# tx.net
KiCad netlist of a schematic drawn in EAGLE
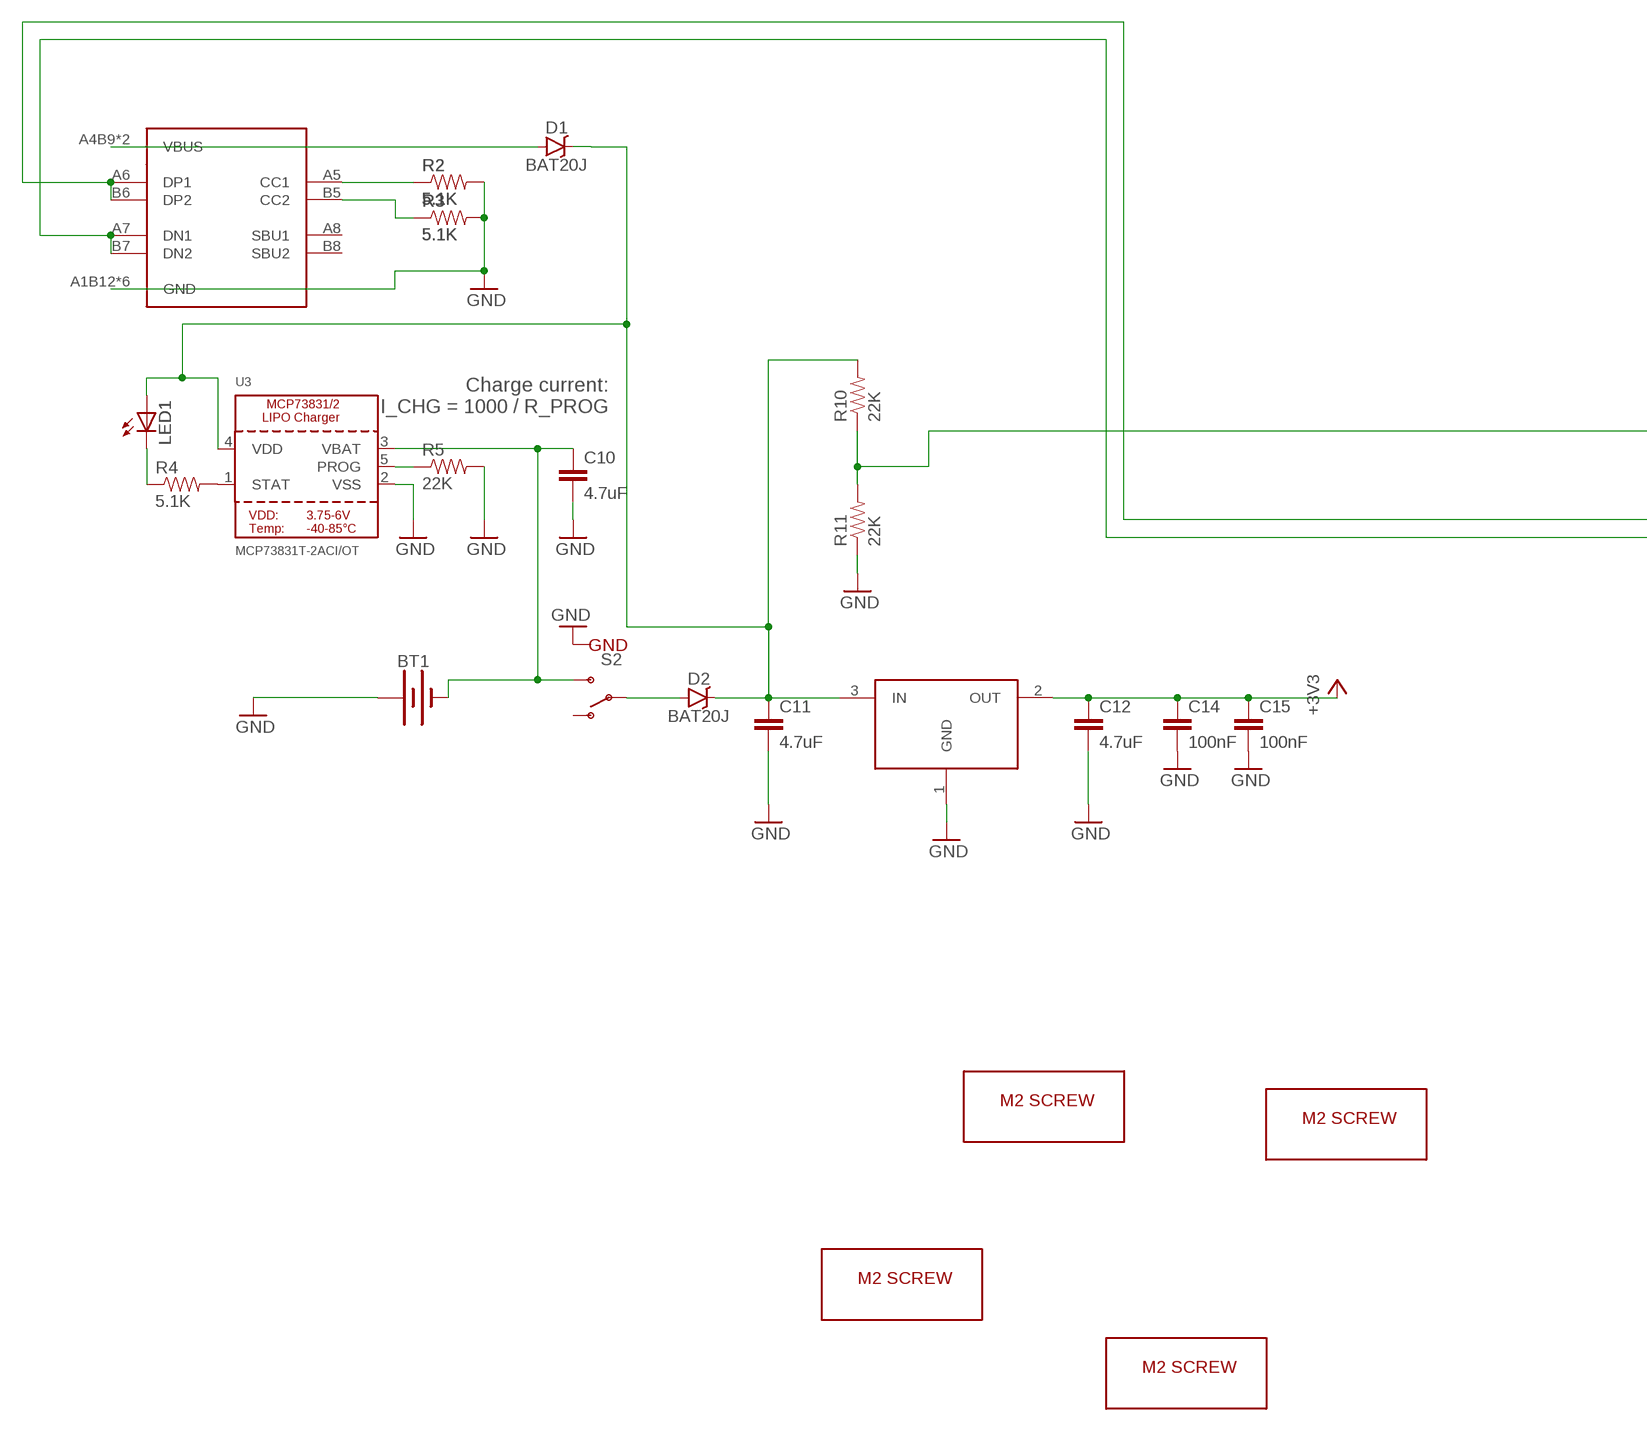
[diagram p0: schematic, sheet 1, part 1 of 2]
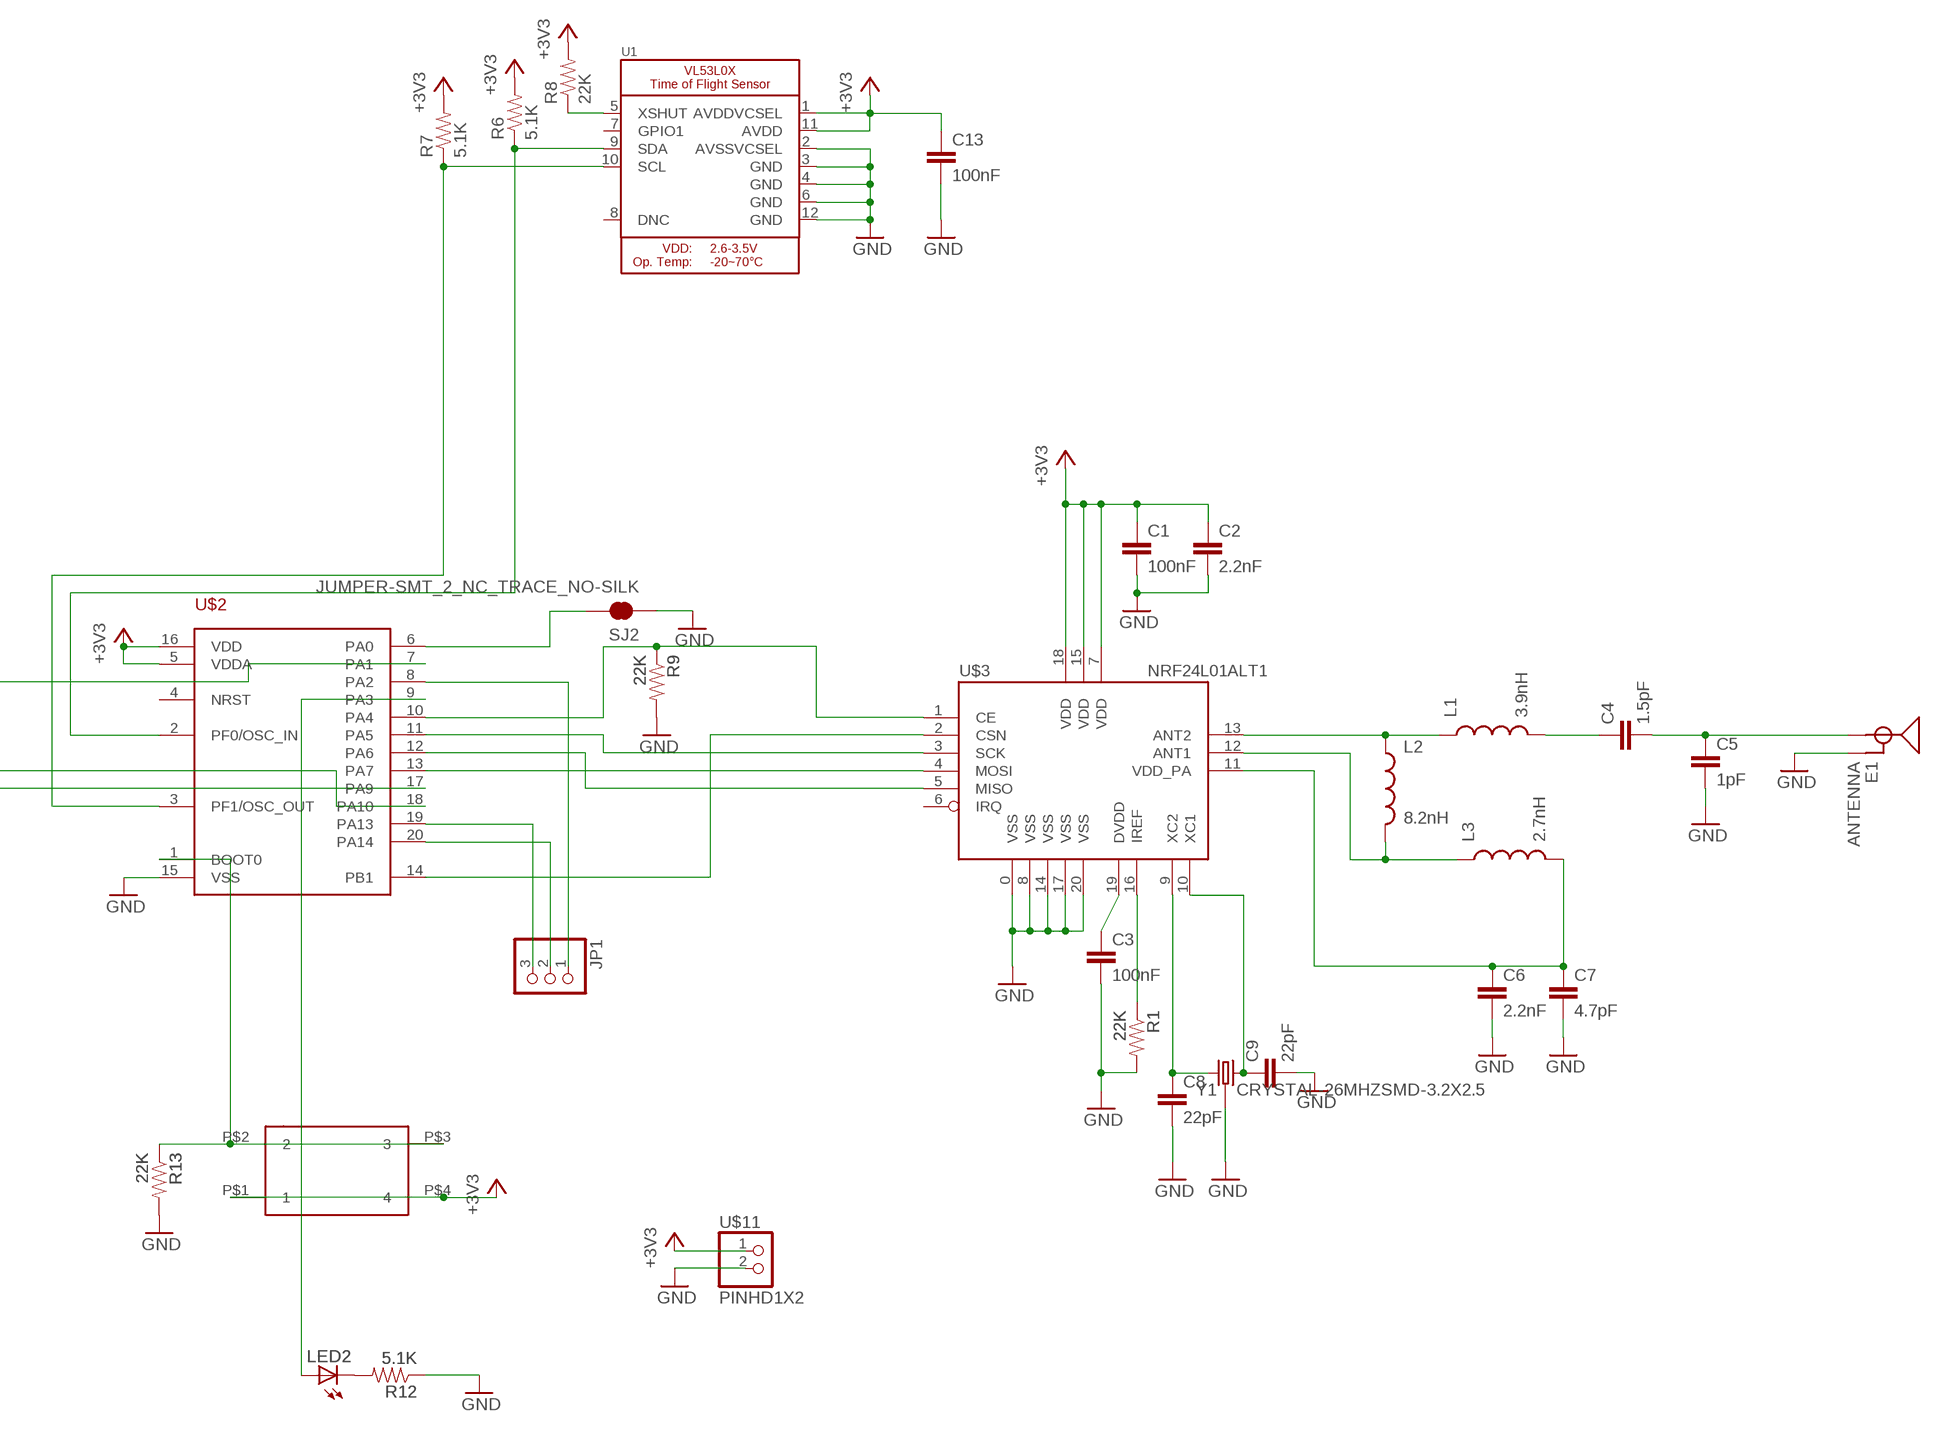
[diagram p1: schematic, sheet 1, part 2 of 2]

(export (version "E")
  (design (tool "Eeschema 10.0.6"))
  (components
    (comp (ref "BT1")
      (value "TX_SPARKFUN-BATTERIES_BATTERY-24.5MM_PTH")
      (footprint "eagle-import:TX_SPARKFUN-BATTERIES_BATTCON_24.5MM_PTH")
      (libsource (lib "eagle-import") (part "TX_SPARKFUN-BATTERIES_BATTERY-24.5MM_PTH"))
    )
    (comp (ref "C1")
      (value "100nF")
      (footprint "eagle-import:0805")
      (libsource (lib "eagle-import") (part "clock_CAP0805"))
    )
    (comp (ref "C2")
      (value "2.2nF")
      (footprint "eagle-import:0805")
      (libsource (lib "eagle-import") (part "clock_CAP0805"))
    )
    (comp (ref "C3")
      (value "100nF")
      (footprint "eagle-import:0805")
      (libsource (lib "eagle-import") (part "clock_CAP0805"))
    )
    (comp (ref "C4")
      (value "1.5pF")
      (footprint "eagle-import:0805")
      (libsource (lib "eagle-import") (part "clock_CAP0805"))
    )
    (comp (ref "C5")
      (value "1pF")
      (footprint "eagle-import:0805")
      (libsource (lib "eagle-import") (part "clock_CAP0805"))
    )
    (comp (ref "C6")
      (value "2.2nF")
      (footprint "eagle-import:0805")
      (libsource (lib "eagle-import") (part "clock_CAP0805"))
    )
    (comp (ref "C7")
      (value "4.7pF")
      (footprint "eagle-import:0805")
      (libsource (lib "eagle-import") (part "clock_CAP0805"))
    )
    (comp (ref "C8")
      (value "22pF")
      (footprint "eagle-import:0805")
      (libsource (lib "eagle-import") (part "clock_CAP0805"))
    )
    (comp (ref "C9")
      (value "22pF")
      (footprint "eagle-import:0805")
      (libsource (lib "eagle-import") (part "clock_CAP0805"))
    )
    (comp (ref "C10")
      (value "4.7uF")
      (footprint "eagle-import:0805")
      (libsource (lib "eagle-import") (part "CAP0805"))
    )
    (comp (ref "C11")
      (value "4.7uF")
      (footprint "eagle-import:0805")
      (libsource (lib "eagle-import") (part "clock_CAP0805"))
    )
    (comp (ref "C12")
      (value "4.7uF")
      (footprint "eagle-import:0805")
      (libsource (lib "eagle-import") (part "clock_CAP0805"))
    )
    (comp (ref "C13")
      (value "100nF")
      (footprint "eagle-import:0805")
      (libsource (lib "eagle-import") (part "clock_CAP0805"))
    )
    (comp (ref "C14")
      (value "100nF")
      (footprint "eagle-import:0805")
      (libsource (lib "eagle-import") (part "clock_CAP0805"))
    )
    (comp (ref "C15")
      (value "100nF")
      (footprint "eagle-import:0805")
      (libsource (lib "eagle-import") (part "clock_CAP0805"))
    )
    (comp (ref "D1")
      (value "BAT20J")
      (footprint "eagle-import:SOD-323")
      (libsource (lib "eagle-import") (part "DIODE-SCHOTTKY-BAT20J"))
    )
    (comp (ref "D2")
      (value "BAT20J")
      (footprint "eagle-import:SOD-323")
      (libsource (lib "eagle-import") (part "DIODE-SCHOTTKY-BAT20J"))
    )
    (comp (ref "E1")
      (value "ANTENNA")
      (footprint "eagle-import:TRACE_ANTENNA_2.4GHZ_25.7MM_TUNED")
      (libsource (lib "eagle-import") (part "ANTENNATRACE-TUNED"))
    )
    (comp (ref "JP1")
      (value "PINHD-1X3CB")
      (footprint "eagle-import:1X03-CLEANBIG")
      (libsource (lib "eagle-import") (part "PINHD-1X3CB"))
    )
    (comp (ref "L1")
      (value "3.9nH")
      (footprint "eagle-import:0805")
      (libsource (lib "eagle-import") (part "INDUCTOR0805"))
    )
    (comp (ref "L2")
      (value "8.2nH")
      (footprint "eagle-import:0805")
      (libsource (lib "eagle-import") (part "INDUCTOR0805"))
    )
    (comp (ref "L3")
      (value "2.7nH")
      (footprint "eagle-import:0805")
      (libsource (lib "eagle-import") (part "INDUCTOR0805"))
    )
    (comp (ref "LED1")
      (value "LEDCHIP-LED0805")
      (footprint "eagle-import:CHIP-LED0805")
      (libsource (lib "eagle-import") (part "LEDCHIP-LED0805"))
    )
    (comp (ref "LED2")
      (value "LEDCHIP-LED0805")
      (footprint "eagle-import:CHIP-LED0805")
      (libsource (lib "eagle-import") (part "LEDCHIP-LED0805"))
    )
    (comp (ref "R1")
      (value "22K")
      (footprint "eagle-import:0805")
      (libsource (lib "eagle-import") (part "joyAnalog_RESISTOR0805-RES"))
    )
    (comp (ref "R2")
      (value "5.1K")
      (footprint "eagle-import:0805")
      (libsource (lib "eagle-import") (part "joyAnalog_RESISTOR0805-RES"))
    )
    (comp (ref "R3")
      (value "5.1K")
      (footprint "eagle-import:0805")
      (libsource (lib "eagle-import") (part "joyAnalog_RESISTOR0805-RES"))
    )
    (comp (ref "R4")
      (value "5.1K")
      (footprint "eagle-import:0805")
      (libsource (lib "eagle-import") (part "RESISTOR0805-RES"))
    )
    (comp (ref "R5")
      (value "22K")
      (footprint "eagle-import:0805")
      (libsource (lib "eagle-import") (part "RESISTOR0805-RES"))
    )
    (comp (ref "R6")
      (value "5.1K")
      (footprint "eagle-import:0805")
      (libsource (lib "eagle-import") (part "RESISTOR0805-RES"))
    )
    (comp (ref "R7")
      (value "5.1K")
      (footprint "eagle-import:0805")
      (libsource (lib "eagle-import") (part "RESISTOR0805-RES"))
    )
    (comp (ref "R8")
      (value "22K")
      (footprint "eagle-import:0805")
      (libsource (lib "eagle-import") (part "RESISTOR0805-RES"))
    )
    (comp (ref "R9")
      (value "22K")
      (footprint "eagle-import:0805")
      (libsource (lib "eagle-import") (part "joyAnalog_RESISTOR0805-RES"))
    )
    (comp (ref "R10")
      (value "22K")
      (footprint "eagle-import:0805")
      (libsource (lib "eagle-import") (part "RESISTOR0805-RES"))
    )
    (comp (ref "R11")
      (value "22K")
      (footprint "eagle-import:0805")
      (libsource (lib "eagle-import") (part "RESISTOR0805-RES"))
    )
    (comp (ref "R12")
      (value "5.1K")
      (footprint "eagle-import:0805")
      (libsource (lib "eagle-import") (part "joyAnalog_RESISTOR0805-RES"))
    )
    (comp (ref "R13")
      (value "22K")
      (footprint "eagle-import:0805")
      (libsource (lib "eagle-import") (part "joyAnalog_RESISTOR0805-RES"))
    )
    (comp (ref "S2")
      (value "SWITCH-SPDTTDFGDFG")
      (footprint "eagle-import:SWITCH-SPST-SMD-A")
      (libsource (lib "eagle-import") (part "SWITCH-SPDTTDFGDFG"))
    )
    (comp (ref "SJ2")
      (value "JUMPER-SMT_2_NC_TRACE_NO-SILK")
      (footprint "eagle-import:SMT-JUMPER_2_NC_TRACE_NO-SILK")
      (libsource (lib "eagle-import") (part "JUMPER-SMT_2_NC_TRACE_NO-SILK"))
    )
    (comp (ref "U$1")
      (value "M2_SCREW_DEV")
      (footprint "eagle-import:M2_SCREW_FOOT")
      (libsource (lib "eagle-import") (part "M2_SCREW_DEV"))
    )
    (comp (ref "U$2")
      (value "STM32F030F4")
      (footprint "eagle-import:TSSOP20")
      (libsource (lib "eagle-import") (part "STM32F030F4"))
    )
    (comp (ref "U$3")
      (value "NRF24L01ALT1")
      (footprint "eagle-import:QFN20_ALT1")
      (libsource (lib "eagle-import") (part "NRF24L01ALT1"))
    )
    (comp (ref "U$4")
      (value "USBC_16P")
      (footprint "eagle-import:USBC_16P_FOOT")
      (libsource (lib "eagle-import") (part "USBC_16P"))
    )
    (comp (ref "U$9")
      (value "XC6206_DEV")
      (footprint "eagle-import:SOT23R_INFINEON")
      (libsource (lib "eagle-import") (part "XC6206_DEV"))
    )
    (comp (ref "U$10")
      (value "324_SW324_SWITCH_FOOT_HOLE")
      (footprint "eagle-import:342_SWICH_FOOT_HOLE")
      (libsource (lib "eagle-import") (part "324_SW324_SWITCH_FOOT_HOLE"))
    )
    (comp (ref "U$11")
      (value "PINHD1X2")
      (footprint "eagle-import:1X02")
      (libsource (lib "eagle-import") (part "PINHD1X2"))
    )
    (comp (ref "U$12")
      (value "M2_SCREW_DEV")
      (footprint "eagle-import:M2_SCREW_FOOT")
      (libsource (lib "eagle-import") (part "M2_SCREW_DEV"))
    )
    (comp (ref "U$13")
      (value "M2_SCREW_DEV")
      (footprint "eagle-import:M2_SCREW_FOOT")
      (libsource (lib "eagle-import") (part "M2_SCREW_DEV"))
    )
    (comp (ref "U$14")
      (value "M2_SCREW_DEV")
      (footprint "eagle-import:M2_SCREW_FOOT")
      (libsource (lib "eagle-import") (part "M2_SCREW_DEV"))
    )
    (comp (ref "U1")
      (value "VL53L0X")
      (footprint "eagle-import:LGA12_ST")
      (libsource (lib "eagle-import") (part "VL53L0X"))
    )
    (comp (ref "U3")
      (value "MCP73831T-2ACI/OT")
      (footprint "eagle-import:SOT23-5")
      (libsource (lib "eagle-import") (part "MCP73831/2"))
    )
    (comp (ref "Y1")
      (value "CRYSTAL-26MHZSMD-3.2X2.5")
      (footprint "eagle-import:CRYSTAL-SMD-3.2X2.5MM")
      (libsource (lib "eagle-import") (part "CRYSTAL-26MHZSMD-3.2X2.5"))
    )
  )
  (nets
    (net (code "1") (name "+3V3") (class "Default")
      (node (ref "C1") (pin "1") (pinfunction "1_1") (pintype "passive"))
      (node (ref "C12") (pin "1") (pinfunction "1_1") (pintype "passive"))
      (node (ref "C13") (pin "1") (pinfunction "1_1") (pintype "passive"))
      (node (ref "C14") (pin "1") (pinfunction "1_1") (pintype "passive"))
      (node (ref "C15") (pin "1") (pinfunction "1_1") (pintype "passive"))
      (node (ref "C2") (pin "1") (pinfunction "1_1") (pintype "passive"))
      (node (ref "R6") (pin "2") (pinfunction "2_2") (pintype "passive"))
      (node (ref "R7") (pin "2") (pinfunction "2_2") (pintype "passive"))
      (node (ref "R8") (pin "2") (pinfunction "2_2") (pintype "passive"))
      (node (ref "U$10") (pin "P$1") (pinfunction "1_P$1") (pintype "bidirectional"))
      (node (ref "U$10") (pin "P$4") (pinfunction "4_P$4") (pintype "bidirectional"))
      (node (ref "U$11") (pin "1") (pinfunction "1_1") (pintype "passive"))
      (node (ref "U$2") (pin "16") (pinfunction "VDD_16") (pintype "bidirectional"))
      (node (ref "U$2") (pin "5") (pinfunction "VDDA_5") (pintype "bidirectional"))
      (node (ref "U$3") (pin "15") (pinfunction "VDD_15") (pintype "power_in"))
      (node (ref "U$3") (pin "18") (pinfunction "VDD_18") (pintype "power_in"))
      (node (ref "U$3") (pin "7") (pinfunction "VDD_7") (pintype "power_in"))
      (node (ref "U$9") (pin "2") (pinfunction "OUT_2") (pintype "bidirectional"))
      (node (ref "U1") (pin "1") (pinfunction "AVDDVCSEL_1") (pintype "power_in"))
      (node (ref "U1") (pin "11") (pinfunction "AVDD_11") (pintype "power_in"))
    )
    (net (code "2") (name "GND") (class "Default")
      (node (ref "BT1") (pin "2") (pinfunction "+_2") (pintype "power_in"))
      (node (ref "C1") (pin "2") (pinfunction "2_2") (pintype "passive"))
      (node (ref "C10") (pin "2") (pinfunction "2_2") (pintype "passive"))
      (node (ref "C11") (pin "2") (pinfunction "2_2") (pintype "passive"))
      (node (ref "C12") (pin "2") (pinfunction "2_2") (pintype "passive"))
      (node (ref "C13") (pin "2") (pinfunction "2_2") (pintype "passive"))
      (node (ref "C14") (pin "2") (pinfunction "2_2") (pintype "passive"))
      (node (ref "C15") (pin "2") (pinfunction "2_2") (pintype "passive"))
      (node (ref "C2") (pin "2") (pinfunction "2_2") (pintype "passive"))
      (node (ref "C3") (pin "2") (pinfunction "2_2") (pintype "passive"))
      (node (ref "C5") (pin "2") (pinfunction "2_2") (pintype "passive"))
      (node (ref "C6") (pin "2") (pinfunction "2_2") (pintype "passive"))
      (node (ref "C7") (pin "2") (pinfunction "2_2") (pintype "passive"))
      (node (ref "C8") (pin "2") (pinfunction "2_2") (pintype "passive"))
      (node (ref "C9") (pin "2") (pinfunction "2_2") (pintype "passive"))
      (node (ref "E1") (pin "GND") (pinfunction "GND_GND") (pintype "bidirectional"))
      (node (ref "E1") (pin "GND2") (pinfunction "GND_GND2") (pintype "bidirectional"))
      (node (ref "R1") (pin "2") (pinfunction "2_2") (pintype "passive"))
      (node (ref "R11") (pin "1") (pinfunction "1_1") (pintype "passive"))
      (node (ref "R12") (pin "1") (pinfunction "1_1") (pintype "passive"))
      (node (ref "R13") (pin "2") (pinfunction "2_2") (pintype "passive"))
      (node (ref "R2") (pin "2") (pinfunction "2_2") (pintype "passive"))
      (node (ref "R3") (pin "2") (pinfunction "2_2") (pintype "passive"))
      (node (ref "R5") (pin "2") (pinfunction "2_2") (pintype "passive"))
      (node (ref "R9") (pin "2") (pinfunction "2_2") (pintype "passive"))
      (node (ref "S2") (pin "G1") (pinfunction "GND_G1") (pintype "passive"))
      (node (ref "S2") (pin "G2") (pinfunction "GND_G2") (pintype "passive"))
      (node (ref "S2") (pin "G3") (pinfunction "GND_G3") (pintype "passive"))
      (node (ref "S2") (pin "G4") (pinfunction "GND_G4") (pintype "passive"))
      (node (ref "SJ2") (pin "1") (pinfunction "1_1") (pintype "passive"))
      (node (ref "U$11") (pin "2") (pinfunction "2_2") (pintype "passive"))
      (node (ref "U$2") (pin "15") (pinfunction "VSS_15") (pintype "bidirectional"))
      (node (ref "U$3") (pin "0") (pinfunction "VSS_0") (pintype "power_in"))
      (node (ref "U$3") (pin "14") (pinfunction "VSS_14") (pintype "power_in"))
      (node (ref "U$3") (pin "17") (pinfunction "VSS_17") (pintype "power_in"))
      (node (ref "U$3") (pin "20") (pinfunction "VSS_20") (pintype "power_in"))
      (node (ref "U$3") (pin "8") (pinfunction "VSS_8") (pintype "power_in"))
      (node (ref "U$4") (pin "A1B12") (pinfunction "GND_A1B12") (pintype "bidirectional"))
      (node (ref "U$4") (pin "B11A12") (pinfunction "GND_B11A12") (pintype "bidirectional"))
      (node (ref "U$4") (pin "P$13") (pinfunction "GND_P$13") (pintype "bidirectional"))
      (node (ref "U$4") (pin "P$14") (pinfunction "GND_P$14") (pintype "bidirectional"))
      (node (ref "U$4") (pin "P$15") (pinfunction "GND_P$15") (pintype "bidirectional"))
      (node (ref "U$4") (pin "P$16") (pinfunction "GND_P$16") (pintype "bidirectional"))
      (node (ref "U$9") (pin "1") (pinfunction "GND_1") (pintype "bidirectional"))
      (node (ref "U1") (pin "12") (pinfunction "GND_12") (pintype "power_in"))
      (node (ref "U1") (pin "2") (pinfunction "AVSSVCSEL_2") (pintype "power_in"))
      (node (ref "U1") (pin "3") (pinfunction "GND_3") (pintype "power_in"))
      (node (ref "U1") (pin "4") (pinfunction "GND_4") (pintype "power_in"))
      (node (ref "U1") (pin "6") (pinfunction "GND_6") (pintype "power_in"))
      (node (ref "U3") (pin "2") (pinfunction "VSS_2") (pintype "power_in"))
      (node (ref "Y1") (pin "2") (pinfunction "3_2") (pintype "passive"))
      (node (ref "Y1") (pin "4") (pinfunction "3_4") (pintype "passive"))
    )
    (net (code "3") (name "Net-(BT1--)") (class "Default")
      (node (ref "BT1") (pin "1") (pinfunction "-_1") (pintype "power_in"))
      (node (ref "C10") (pin "1") (pinfunction "1_1") (pintype "passive"))
      (node (ref "S2") (pin "3") (pinfunction "S_3") (pintype "passive"))
      (node (ref "U3") (pin "3") (pinfunction "VBAT_3") (pintype "power_in"))
    )
    (net (code "4") (name "Net-(C4-Pad1)") (class "Default")
      (node (ref "C4") (pin "1") (pinfunction "1_1") (pintype "passive"))
      (node (ref "L1") (pin "2") (pinfunction "2_2") (pintype "passive"))
    )
    (net (code "5") (name "Net-(D1-PadA)") (class "Default")
      (node (ref "D1") (pin "A") (pinfunction "A_A") (pintype "passive"))
      (node (ref "U$4") (pin "A4B9") (pinfunction "VBUS_A4B9") (pintype "bidirectional"))
      (node (ref "U$4") (pin "B4A9") (pinfunction "VBUS_B4A9") (pintype "bidirectional"))
    )
    (net (code "6") (name "Net-(E1-SIGNAL)") (class "Default")
      (node (ref "C4") (pin "2") (pinfunction "2_2") (pintype "passive"))
      (node (ref "C5") (pin "1") (pinfunction "1_1") (pintype "passive"))
      (node (ref "E1") (pin "ANT") (pinfunction "SIGNAL_ANT") (pintype "bidirectional"))
    )
    (net (code "7") (name "Net-(LED1-PadC)") (class "Default")
      (node (ref "LED1") (pin "C") (pinfunction "C_C") (pintype "passive"))
      (node (ref "R4") (pin "1") (pinfunction "1_1") (pintype "passive"))
    )
    (net (code "8") (name "Net-(LED2-PadC)") (class "Default")
      (node (ref "LED2") (pin "C") (pinfunction "C_C") (pintype "passive"))
      (node (ref "R12") (pin "2") (pinfunction "2_2") (pintype "passive"))
    )
    (net (code "9") (name "Net-(S2-P)") (class "Default")
      (node (ref "D2") (pin "A") (pinfunction "A_A") (pintype "passive"))
      (node (ref "S2") (pin "2") (pinfunction "P_2") (pintype "passive"))
    )
    (net (code "10") (name "Net-(U$2-PA0)") (class "Default")
      (node (ref "SJ2") (pin "2") (pinfunction "2_2") (pintype "passive"))
      (node (ref "U$2") (pin "6") (pinfunction "PA0_6") (pintype "bidirectional"))
    )
    (net (code "11") (name "Net-(U$2-PA1)") (class "Default")
      (node (ref "R10") (pin "1") (pinfunction "1_1") (pintype "passive"))
      (node (ref "R11") (pin "2") (pinfunction "2_2") (pintype "passive"))
      (node (ref "U$2") (pin "7") (pinfunction "PA1_7") (pintype "bidirectional"))
    )
    (net (code "12") (name "Net-(U$2-PA2)") (class "Default")
      (node (ref "JP1") (pin "1") (pinfunction "1_1") (pintype "passive"))
      (node (ref "U$2") (pin "8") (pinfunction "PA2_8") (pintype "bidirectional"))
    )
    (net (code "13") (name "Net-(U$2-PA3)") (class "Default")
      (node (ref "LED2") (pin "A") (pinfunction "A_A") (pintype "passive"))
      (node (ref "U$2") (pin "9") (pinfunction "PA3_9") (pintype "bidirectional"))
    )
    (net (code "14") (name "Net-(U$2-PA4)") (class "Default")
      (node (ref "R9") (pin "1") (pinfunction "1_1") (pintype "passive"))
      (node (ref "U$2") (pin "10") (pinfunction "PA4_10") (pintype "bidirectional"))
      (node (ref "U$3") (pin "1") (pinfunction "CE_1") (pintype "input"))
    )
    (net (code "15") (name "Net-(U$2-PA5)") (class "Default")
      (node (ref "U$2") (pin "11") (pinfunction "PA5_11") (pintype "bidirectional"))
      (node (ref "U$3") (pin "3") (pinfunction "SCK_3") (pintype "input"))
    )
    (net (code "16") (name "Net-(U$2-PA6)") (class "Default")
      (node (ref "U$2") (pin "12") (pinfunction "PA6_12") (pintype "bidirectional"))
      (node (ref "U$3") (pin "5") (pinfunction "MISO_5") (pintype "output"))
    )
    (net (code "17") (name "Net-(U$2-PA7)") (class "Default")
      (node (ref "U$2") (pin "13") (pinfunction "PA7_13") (pintype "bidirectional"))
      (node (ref "U$3") (pin "4") (pinfunction "MOSI_4") (pintype "input"))
    )
    (net (code "18") (name "Net-(U$2-PA9)") (class "Default")
      (node (ref "U$2") (pin "17") (pinfunction "PA9_17") (pintype "bidirectional"))
      (node (ref "U$4") (pin "A7") (pinfunction "DN1_A7") (pintype "bidirectional"))
      (node (ref "U$4") (pin "B7") (pinfunction "DN2_B7") (pintype "bidirectional"))
    )
    (net (code "19") (name "Net-(U$2-PA10)") (class "Default")
      (node (ref "U$2") (pin "18") (pinfunction "PA10_18") (pintype "bidirectional"))
      (node (ref "U$4") (pin "A6") (pinfunction "DP1_A6") (pintype "bidirectional"))
      (node (ref "U$4") (pin "B6") (pinfunction "DP2_B6") (pintype "bidirectional"))
    )
    (net (code "20") (name "Net-(U$2-PA13)") (class "Default")
      (node (ref "JP1") (pin "3") (pinfunction "3_3") (pintype "passive"))
      (node (ref "U$2") (pin "19") (pinfunction "PA13_19") (pintype "bidirectional"))
    )
    (net (code "21") (name "Net-(U$2-PA14)") (class "Default")
      (node (ref "JP1") (pin "2") (pinfunction "2_2") (pintype "passive"))
      (node (ref "U$2") (pin "20") (pinfunction "PA14_20") (pintype "bidirectional"))
    )
    (net (code "22") (name "Net-(U$2-PB1)") (class "Default")
      (node (ref "U$2") (pin "14") (pinfunction "PB1_14") (pintype "bidirectional"))
      (node (ref "U$3") (pin "2") (pinfunction "CSN_2") (pintype "input"))
    )
    (net (code "23") (name "Net-(U$2-PF0{slash}OSC_IN)") (class "Default")
      (node (ref "R6") (pin "1") (pinfunction "1_1") (pintype "passive"))
      (node (ref "U$2") (pin "2") (pinfunction "PF0/OSC_IN_2") (pintype "bidirectional"))
      (node (ref "U1") (pin "9") (pinfunction "SDA_9") (pintype "open_collector"))
    )
    (net (code "24") (name "Net-(U$2-PF1{slash}OSC_OUT)") (class "Default")
      (node (ref "R7") (pin "1") (pinfunction "1_1") (pintype "passive"))
      (node (ref "U$2") (pin "3") (pinfunction "PF1/OSC_OUT_3") (pintype "bidirectional"))
      (node (ref "U1") (pin "10") (pinfunction "SCL_10") (pintype "open_collector"))
    )
    (net (code "25") (name "Net-(U$3-ANT1)") (class "Default")
      (node (ref "L2") (pin "2") (pinfunction "2_2") (pintype "passive"))
      (node (ref "L3") (pin "1") (pinfunction "1_1") (pintype "passive"))
      (node (ref "U$3") (pin "12") (pinfunction "ANT1_12") (pintype "output"))
    )
    (net (code "26") (name "Net-(U$3-ANT2)") (class "Default")
      (node (ref "L1") (pin "1") (pinfunction "1_1") (pintype "passive"))
      (node (ref "L2") (pin "1") (pinfunction "1_1") (pintype "passive"))
      (node (ref "U$3") (pin "13") (pinfunction "ANT2_13") (pintype "output"))
    )
    (net (code "27") (name "Net-(U$3-DVDD)") (class "Default")
      (node (ref "C3") (pin "1") (pinfunction "1_1") (pintype "passive"))
      (node (ref "U$3") (pin "19") (pinfunction "DVDD_19") (pintype "power_in"))
    )
    (net (code "28") (name "Net-(U$3-IREF)") (class "Default")
      (node (ref "R1") (pin "1") (pinfunction "1_1") (pintype "passive"))
      (node (ref "U$3") (pin "16") (pinfunction "IREF_16") (pintype "input"))
    )
    (net (code "29") (name "Net-(U$3-VDD_PA)") (class "Default")
      (node (ref "C6") (pin "1") (pinfunction "1_1") (pintype "passive"))
      (node (ref "C7") (pin "1") (pinfunction "1_1") (pintype "passive"))
      (node (ref "L3") (pin "2") (pinfunction "2_2") (pintype "passive"))
      (node (ref "U$3") (pin "11") (pinfunction "VDD_PA_11") (pintype "power_in"))
    )
    (net (code "30") (name "Net-(U$3-XC1)") (class "Default")
      (node (ref "C9") (pin "1") (pinfunction "1_1") (pintype "passive"))
      (node (ref "U$3") (pin "10") (pinfunction "XC1_10") (pintype "input"))
      (node (ref "Y1") (pin "3") (pinfunction "2_3") (pintype "passive"))
    )
    (net (code "31") (name "Net-(U$3-XC2)") (class "Default")
      (node (ref "C8") (pin "1") (pinfunction "1_1") (pintype "passive"))
      (node (ref "U$3") (pin "9") (pinfunction "XC2_9") (pintype "input"))
      (node (ref "Y1") (pin "1") (pinfunction "1_1") (pintype "passive"))
    )
    (net (code "32") (name "Net-(U$4-CC1)") (class "Default")
      (node (ref "R2") (pin "1") (pinfunction "1_1") (pintype "passive"))
      (node (ref "U$4") (pin "A5") (pinfunction "CC1_A5") (pintype "bidirectional"))
    )
    (net (code "33") (name "Net-(U$4-CC2)") (class "Default")
      (node (ref "R3") (pin "1") (pinfunction "1_1") (pintype "passive"))
      (node (ref "U$4") (pin "B5") (pinfunction "CC2_B5") (pintype "bidirectional"))
    )
    (net (code "34") (name "Net-(U$9-IN)") (class "Default")
      (node (ref "C11") (pin "1") (pinfunction "1_1") (pintype "passive"))
      (node (ref "D1") (pin "C") (pinfunction "C_C") (pintype "passive"))
      (node (ref "D2") (pin "C") (pinfunction "C_C") (pintype "passive"))
      (node (ref "LED1") (pin "A") (pinfunction "A_A") (pintype "passive"))
      (node (ref "R10") (pin "2") (pinfunction "2_2") (pintype "passive"))
      (node (ref "U$9") (pin "3") (pinfunction "IN_3") (pintype "bidirectional"))
      (node (ref "U3") (pin "4") (pinfunction "VDD_4") (pintype "power_in"))
    )
    (net (code "35") (name "Net-(U$10-2)") (class "Default")
      (node (ref "R13") (pin "1") (pinfunction "1_1") (pintype "passive"))
      (node (ref "U$10") (pin "P$2") (pinfunction "2_P$2") (pintype "bidirectional"))
      (node (ref "U$10") (pin "P$3") (pinfunction "3_P$3") (pintype "bidirectional"))
      (node (ref "U$2") (pin "1") (pinfunction "BOOT0_1") (pintype "bidirectional"))
    )
    (net (code "36") (name "Net-(U1-XSHUT)") (class "Default")
      (node (ref "R8") (pin "1") (pinfunction "1_1") (pintype "passive"))
      (node (ref "U1") (pin "5") (pinfunction "XSHUT_5") (pintype "input"))
    )
    (net (code "37") (name "Net-(U3-PROG)") (class "Default")
      (node (ref "R5") (pin "1") (pinfunction "1_1") (pintype "passive"))
      (node (ref "U3") (pin "5") (pinfunction "PROG_5") (pintype "input"))
    )
    (net (code "38") (name "Net-(U3-STAT)") (class "Default")
      (node (ref "R4") (pin "2") (pinfunction "2_2") (pintype "passive"))
      (node (ref "U3") (pin "1") (pinfunction "STAT_1") (pintype "output"))
    )
    (net (code "39") (name "unconnected-(S2-O-Pad1)") (class "Default")
      (node (ref "S2") (pin "1") (pinfunction "O_1") (pintype "passive"))
    )
    (net (code "40") (name "unconnected-(U$2-NRST-Pad4)") (class "Default")
      (node (ref "U$2") (pin "4") (pinfunction "NRST_4") (pintype "bidirectional"))
    )
    (net (code "41") (name "unconnected-(U$3-IRQ-Pad6)") (class "Default")
      (node (ref "U$3") (pin "6") (pinfunction "IRQ_6") (pintype "output"))
    )
    (net (code "42") (name "unconnected-(U$4-SBU1-PadA8)") (class "Default")
      (node (ref "U$4") (pin "A8") (pinfunction "SBU1_A8") (pintype "bidirectional"))
    )
    (net (code "43") (name "unconnected-(U$4-SBU2-PadB8)") (class "Default")
      (node (ref "U$4") (pin "B8") (pinfunction "SBU2_B8") (pintype "bidirectional"))
    )
    (net (code "44") (name "unconnected-(U1-DNC-Pad8)") (class "Default")
      (node (ref "U1") (pin "8") (pinfunction "DNC_8") (pintype "no_connect"))
    )
    (net (code "45") (name "unconnected-(U1-GPIO1-Pad7)") (class "Default")
      (node (ref "U1") (pin "7") (pinfunction "GPIO1_7") (pintype "output"))
    )
  )
)
